# PCB_-_Pro_Micro.net
KiCad netlist of a schematic drawn in EAGLE
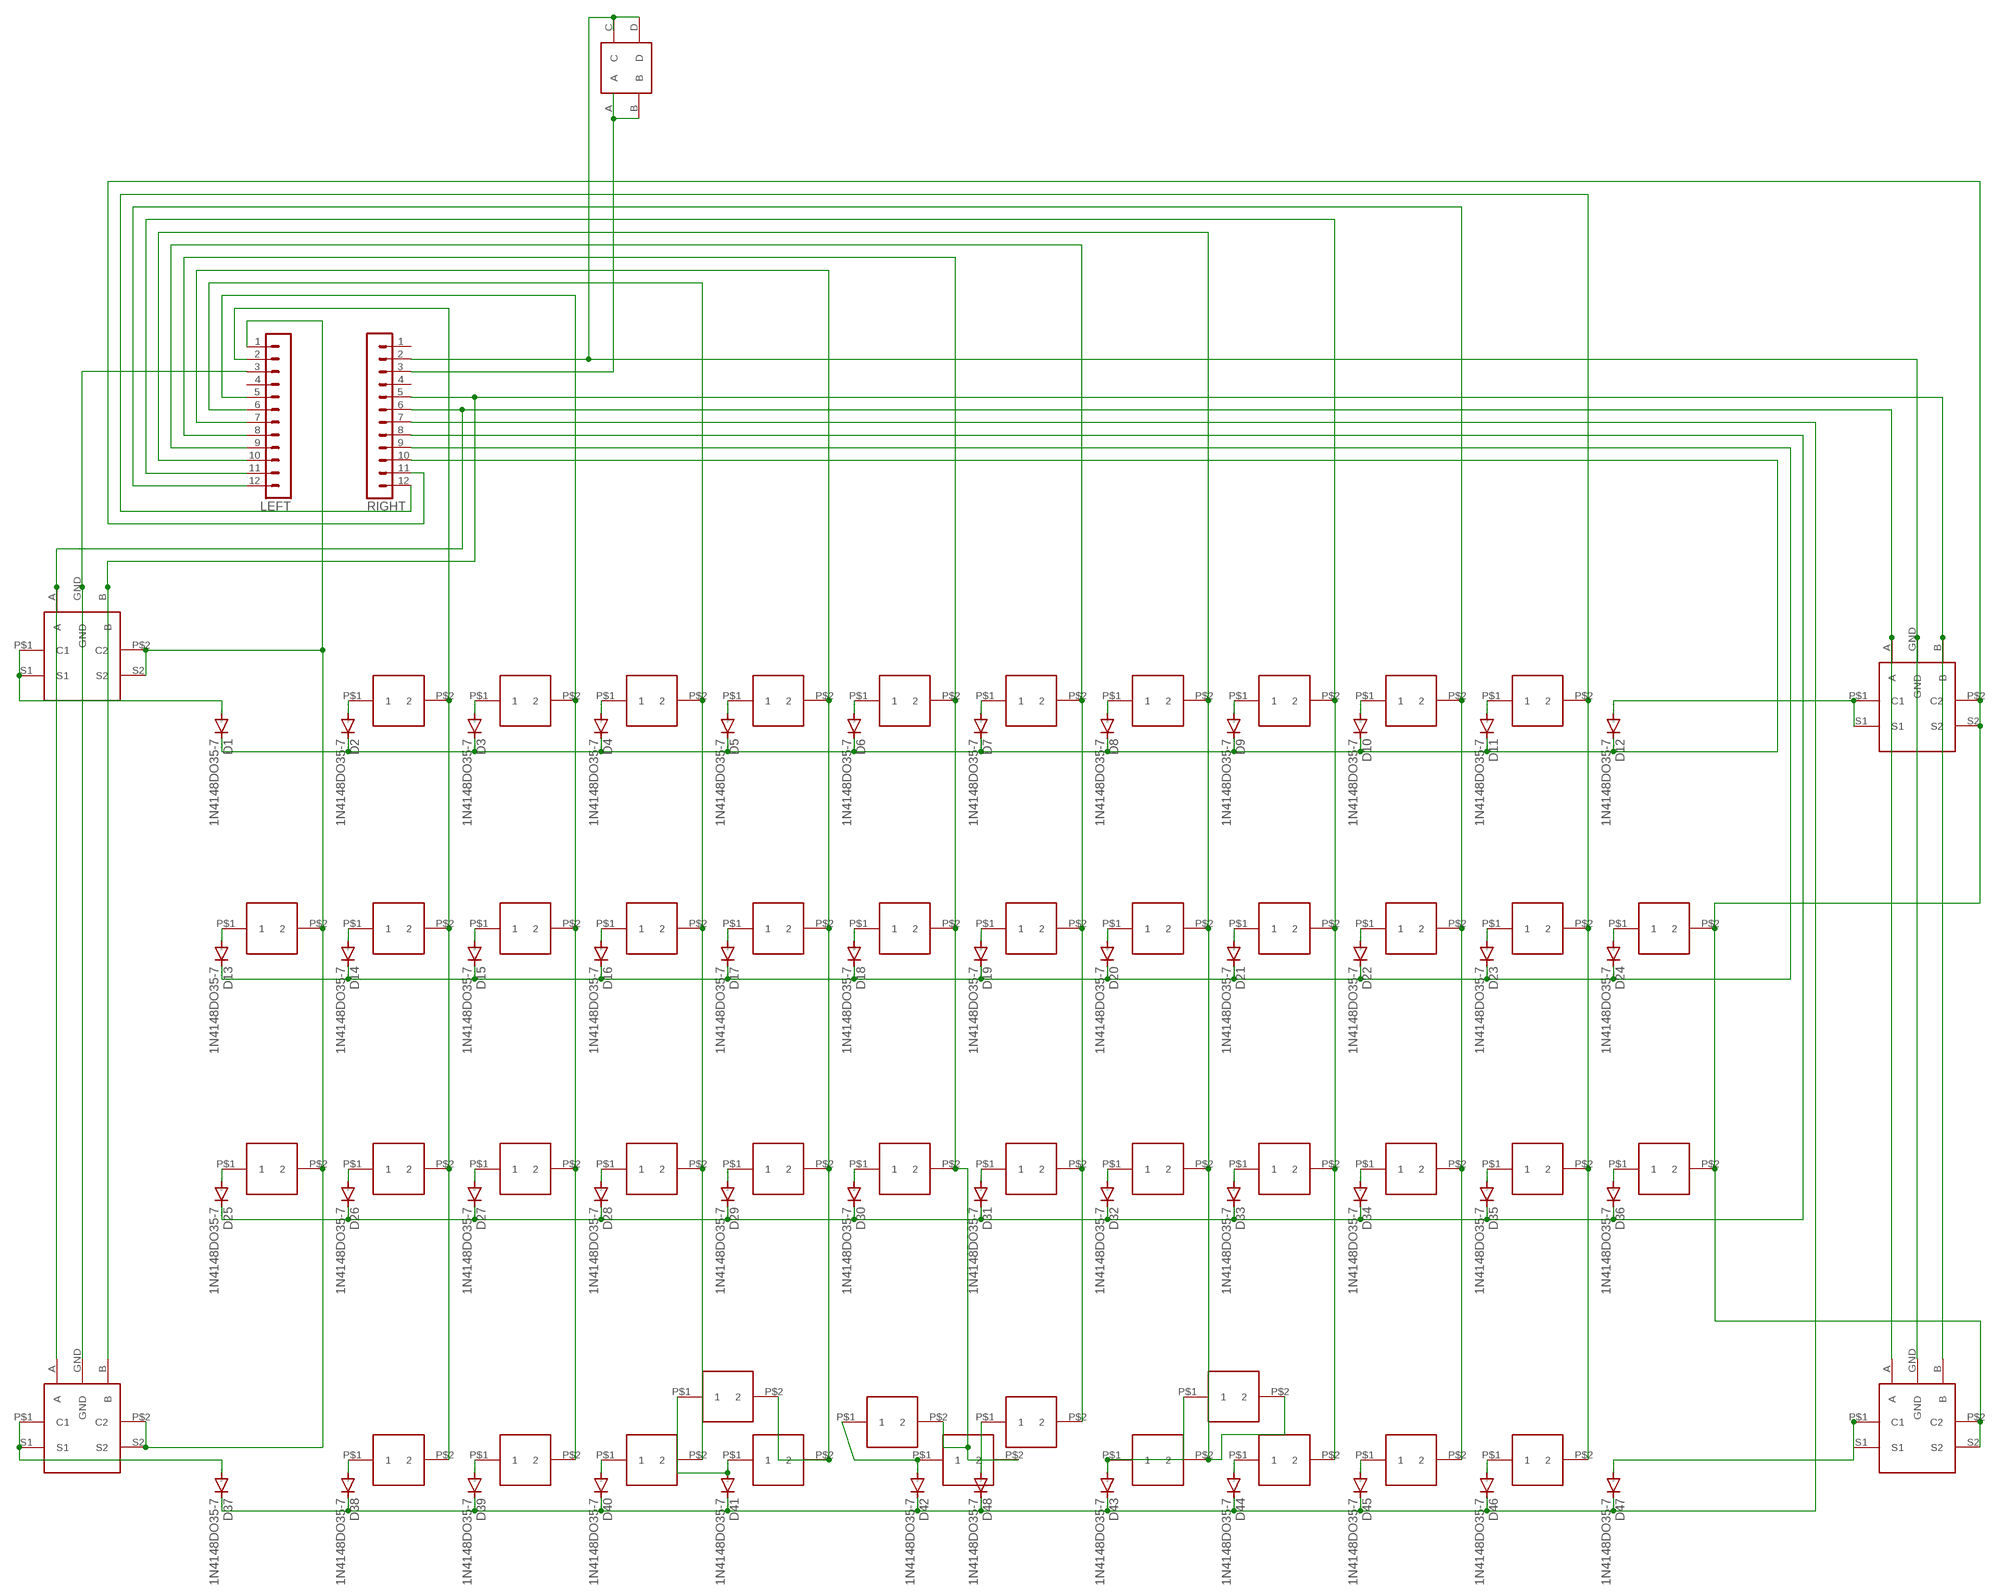
[diagram p0: schematic, sheet 1]

(export (version "E")
  (design (tool "Eeschema 10.0.6"))
  (components
    (comp (ref "1")
      (value "CHERRY-SOLDER")
      (footprint "eagle-import:CHERRY-SOLDER")
      (libsource (lib "eagle-import") (part "CHERRY-SOLDER"))
    )
    (comp (ref "2")
      (value "CHERRY-SOLDER")
      (footprint "eagle-import:CHERRY-SOLDER")
      (libsource (lib "eagle-import") (part "CHERRY-SOLDER"))
    )
    (comp (ref "3")
      (value "CHERRY-SOLDER")
      (footprint "eagle-import:CHERRY-SOLDER")
      (libsource (lib "eagle-import") (part "CHERRY-SOLDER"))
    )
    (comp (ref "4")
      (value "CHERRY-SOLDER")
      (footprint "eagle-import:CHERRY-SOLDER")
      (libsource (lib "eagle-import") (part "CHERRY-SOLDER"))
    )
    (comp (ref "12")
      (value "CHERRY-SOLDER")
      (footprint "eagle-import:CHERRY-SOLDER")
      (libsource (lib "eagle-import") (part "CHERRY-SOLDER"))
    )
    (comp (ref "13")
      (value "CHERRY-SOLDER")
      (footprint "eagle-import:CHERRY-SOLDER")
      (libsource (lib "eagle-import") (part "CHERRY-SOLDER"))
    )
    (comp (ref "14")
      (value "CHERRY-SOLDER")
      (footprint "eagle-import:CHERRY-SOLDER")
      (libsource (lib "eagle-import") (part "CHERRY-SOLDER"))
    )
    (comp (ref "15")
      (value "CHERRY-SOLDER")
      (footprint "eagle-import:CHERRY-SOLDER")
      (libsource (lib "eagle-import") (part "CHERRY-SOLDER"))
    )
    (comp (ref "16")
      (value "CHERRY-SOLDER")
      (footprint "eagle-import:CHERRY-SOLDER")
      (libsource (lib "eagle-import") (part "CHERRY-SOLDER"))
    )
    (comp (ref "17")
      (value "CHERRY-SOLDER")
      (footprint "eagle-import:CHERRY-SOLDER")
      (libsource (lib "eagle-import") (part "CHERRY-SOLDER"))
    )
    (comp (ref "18")
      (value "CHERRY-SOLDER")
      (footprint "eagle-import:CHERRY-SOLDER")
      (libsource (lib "eagle-import") (part "CHERRY-SOLDER"))
    )
    (comp (ref "19")
      (value "CHERRY-SOLDER")
      (footprint "eagle-import:CHERRY-SOLDER")
      (libsource (lib "eagle-import") (part "CHERRY-SOLDER"))
    )
    (comp (ref "21")
      (value "CHERRY-SOLDER")
      (footprint "eagle-import:CHERRY-SOLDER")
      (libsource (lib "eagle-import") (part "CHERRY-SOLDER"))
    )
    (comp (ref "22")
      (value "CHERRY-SOLDER")
      (footprint "eagle-import:CHERRY-SOLDER")
      (libsource (lib "eagle-import") (part "CHERRY-SOLDER"))
    )
    (comp (ref "23")
      (value "CHERRY-SOLDER")
      (footprint "eagle-import:CHERRY-SOLDER")
      (libsource (lib "eagle-import") (part "CHERRY-SOLDER"))
    )
    (comp (ref "24")
      (value "CHERRY-SOLDER")
      (footprint "eagle-import:CHERRY-SOLDER")
      (libsource (lib "eagle-import") (part "CHERRY-SOLDER"))
    )
    (comp (ref "25")
      (value "CHERRY-SOLDER")
      (footprint "eagle-import:CHERRY-SOLDER")
      (libsource (lib "eagle-import") (part "CHERRY-SOLDER"))
    )
    (comp (ref "26")
      (value "CHERRY-SOLDER")
      (footprint "eagle-import:CHERRY-SOLDER")
      (libsource (lib "eagle-import") (part "CHERRY-SOLDER"))
    )
    (comp (ref "27")
      (value "CHERRY-SOLDER")
      (footprint "eagle-import:CHERRY-SOLDER")
      (libsource (lib "eagle-import") (part "CHERRY-SOLDER"))
    )
    (comp (ref "28")
      (value "CHERRY-SOLDER")
      (footprint "eagle-import:CHERRY-SOLDER")
      (libsource (lib "eagle-import") (part "CHERRY-SOLDER"))
    )
    (comp (ref "29")
      (value "CHERRY-SOLDER")
      (footprint "eagle-import:CHERRY-SOLDER")
      (libsource (lib "eagle-import") (part "CHERRY-SOLDER"))
    )
    (comp (ref "31")
      (value "CHERRY-SOLDER")
      (footprint "eagle-import:CHERRY-SOLDER")
      (libsource (lib "eagle-import") (part "CHERRY-SOLDER"))
    )
    (comp (ref "32")
      (value "CHERRY-SOLDER")
      (footprint "eagle-import:CHERRY-SOLDER")
      (libsource (lib "eagle-import") (part "CHERRY-SOLDER"))
    )
    (comp (ref "33")
      (value "CHERRY-SOLDER")
      (footprint "eagle-import:CHERRY-SOLDER")
      (libsource (lib "eagle-import") (part "CHERRY-SOLDER"))
    )
    (comp (ref "34")
      (value "CHERRY-SOLDER")
      (footprint "eagle-import:CHERRY-SOLDER")
      (libsource (lib "eagle-import") (part "CHERRY-SOLDER"))
    )
    (comp (ref "35")
      (value "CHERRY-SOLDER")
      (footprint "eagle-import:CHERRY-SOLDER")
      (libsource (lib "eagle-import") (part "CHERRY-SOLDER"))
    )
    (comp (ref "36")
      (value "CHERRY-SOLDER")
      (footprint "eagle-import:CHERRY-SOLDER")
      (libsource (lib "eagle-import") (part "CHERRY-SOLDER"))
    )
    (comp (ref "37")
      (value "CHERRY-SOLDER")
      (footprint "eagle-import:CHERRY-SOLDER")
      (libsource (lib "eagle-import") (part "CHERRY-SOLDER"))
    )
    (comp (ref "38")
      (value "CHERRY-SOLDER")
      (footprint "eagle-import:CHERRY-SOLDER")
      (libsource (lib "eagle-import") (part "CHERRY-SOLDER"))
    )
    (comp (ref "39")
      (value "CHERRY-SOLDER")
      (footprint "eagle-import:CHERRY-SOLDER")
      (libsource (lib "eagle-import") (part "CHERRY-SOLDER"))
    )
    (comp (ref "42")
      (value "CHERRY-SOLDER")
      (footprint "eagle-import:CHERRY-SOLDER")
      (libsource (lib "eagle-import") (part "CHERRY-SOLDER"))
    )
    (comp (ref "43")
      (value "CHERRY-SOLDER")
      (footprint "eagle-import:CHERRY-SOLDER")
      (libsource (lib "eagle-import") (part "CHERRY-SOLDER"))
    )
    (comp (ref "44")
      (value "CHERRY-SOLDER")
      (footprint "eagle-import:CHERRY-SOLDER")
      (libsource (lib "eagle-import") (part "CHERRY-SOLDER"))
    )
    (comp (ref "45")
      (value "CHERRY-SOLDER")
      (footprint "eagle-import:CHERRY-SOLDER")
      (libsource (lib "eagle-import") (part "CHERRY-SOLDER"))
    )
    (comp (ref "46")
      (value "CHERRY-SOLDER")
      (footprint "eagle-import:CHERRY-SOLDER")
      (libsource (lib "eagle-import") (part "CHERRY-SOLDER"))
    )
    (comp (ref "47")
      (value "CHERRY-SOLDER")
      (footprint "eagle-import:CHERRY-SOLDER")
      (libsource (lib "eagle-import") (part "CHERRY-SOLDER"))
    )
    (comp (ref "48")
      (value "CHERRY-SOLDER")
      (footprint "eagle-import:CHERRY-SOLDER")
      (libsource (lib "eagle-import") (part "CHERRY-SOLDER"))
    )
    (comp (ref "49")
      (value "CHERRY-SOLDER")
      (footprint "eagle-import:CHERRY-SOLDER")
      (libsource (lib "eagle-import") (part "CHERRY-SOLDER"))
    )
    (comp (ref "110")
      (value "CHERRY-SOLDER")
      (footprint "eagle-import:CHERRY-SOLDER")
      (libsource (lib "eagle-import") (part "CHERRY-SOLDER"))
    )
    (comp (ref "111")
      (value "CHERRY-SOLDER")
      (footprint "eagle-import:CHERRY-SOLDER")
      (libsource (lib "eagle-import") (part "CHERRY-SOLDER"))
    )
    (comp (ref "210")
      (value "CHERRY-SOLDER")
      (footprint "eagle-import:CHERRY-SOLDER")
      (libsource (lib "eagle-import") (part "CHERRY-SOLDER"))
    )
    (comp (ref "211")
      (value "CHERRY-SOLDER")
      (footprint "eagle-import:CHERRY-SOLDER")
      (libsource (lib "eagle-import") (part "CHERRY-SOLDER"))
    )
    (comp (ref "212")
      (value "CHERRY-SOLDER")
      (footprint "eagle-import:CHERRY-SOLDER")
      (libsource (lib "eagle-import") (part "CHERRY-SOLDER"))
    )
    (comp (ref "310")
      (value "CHERRY-SOLDER")
      (footprint "eagle-import:CHERRY-SOLDER")
      (libsource (lib "eagle-import") (part "CHERRY-SOLDER"))
    )
    (comp (ref "311")
      (value "CHERRY-SOLDER")
      (footprint "eagle-import:CHERRY-SOLDER")
      (libsource (lib "eagle-import") (part "CHERRY-SOLDER"))
    )
    (comp (ref "312")
      (value "CHERRY-SOLDER")
      (footprint "eagle-import:CHERRY-SOLDER")
      (libsource (lib "eagle-import") (part "CHERRY-SOLDER"))
    )
    (comp (ref "410")
      (value "CHERRY-SOLDER")
      (footprint "eagle-import:CHERRY-SOLDER")
      (libsource (lib "eagle-import") (part "CHERRY-SOLDER"))
    )
    (comp (ref "D1")
      (value "1N4148DO35-7")
      (footprint "eagle-import:DO35-7")
      (libsource (lib "eagle-import") (part "1N4148DO35-7"))
    )
    (comp (ref "D2")
      (value "1N4148DO35-7")
      (footprint "eagle-import:DO35-7")
      (libsource (lib "eagle-import") (part "1N4148DO35-7"))
    )
    (comp (ref "D3")
      (value "1N4148DO35-7")
      (footprint "eagle-import:DO35-7")
      (libsource (lib "eagle-import") (part "1N4148DO35-7"))
    )
    (comp (ref "D4")
      (value "1N4148DO35-7")
      (footprint "eagle-import:DO35-7")
      (libsource (lib "eagle-import") (part "1N4148DO35-7"))
    )
    (comp (ref "D5")
      (value "1N4148DO35-7")
      (footprint "eagle-import:DO35-7")
      (libsource (lib "eagle-import") (part "1N4148DO35-7"))
    )
    (comp (ref "D6")
      (value "1N4148DO35-7")
      (footprint "eagle-import:DO35-7")
      (libsource (lib "eagle-import") (part "1N4148DO35-7"))
    )
    (comp (ref "D7")
      (value "1N4148DO35-7")
      (footprint "eagle-import:DO35-7")
      (libsource (lib "eagle-import") (part "1N4148DO35-7"))
    )
    (comp (ref "D8")
      (value "1N4148DO35-7")
      (footprint "eagle-import:DO35-7")
      (libsource (lib "eagle-import") (part "1N4148DO35-7"))
    )
    (comp (ref "D9")
      (value "1N4148DO35-7")
      (footprint "eagle-import:DO35-7")
      (libsource (lib "eagle-import") (part "1N4148DO35-7"))
    )
    (comp (ref "D10")
      (value "1N4148DO35-7")
      (footprint "eagle-import:DO35-7")
      (libsource (lib "eagle-import") (part "1N4148DO35-7"))
    )
    (comp (ref "D11")
      (value "1N4148DO35-7")
      (footprint "eagle-import:DO35-7")
      (libsource (lib "eagle-import") (part "1N4148DO35-7"))
    )
    (comp (ref "D12")
      (value "1N4148DO35-7")
      (footprint "eagle-import:DO35-7")
      (libsource (lib "eagle-import") (part "1N4148DO35-7"))
    )
    (comp (ref "D13")
      (value "1N4148DO35-7")
      (footprint "eagle-import:DO35-7")
      (libsource (lib "eagle-import") (part "1N4148DO35-7"))
    )
    (comp (ref "D14")
      (value "1N4148DO35-7")
      (footprint "eagle-import:DO35-7")
      (libsource (lib "eagle-import") (part "1N4148DO35-7"))
    )
    (comp (ref "D15")
      (value "1N4148DO35-7")
      (footprint "eagle-import:DO35-7")
      (libsource (lib "eagle-import") (part "1N4148DO35-7"))
    )
    (comp (ref "D16")
      (value "1N4148DO35-7")
      (footprint "eagle-import:DO35-7")
      (libsource (lib "eagle-import") (part "1N4148DO35-7"))
    )
    (comp (ref "D17")
      (value "1N4148DO35-7")
      (footprint "eagle-import:DO35-7")
      (libsource (lib "eagle-import") (part "1N4148DO35-7"))
    )
    (comp (ref "D18")
      (value "1N4148DO35-7")
      (footprint "eagle-import:DO35-7")
      (libsource (lib "eagle-import") (part "1N4148DO35-7"))
    )
    (comp (ref "D19")
      (value "1N4148DO35-7")
      (footprint "eagle-import:DO35-7")
      (libsource (lib "eagle-import") (part "1N4148DO35-7"))
    )
    (comp (ref "D20")
      (value "1N4148DO35-7")
      (footprint "eagle-import:DO35-7")
      (libsource (lib "eagle-import") (part "1N4148DO35-7"))
    )
    (comp (ref "D21")
      (value "1N4148DO35-7")
      (footprint "eagle-import:DO35-7")
      (libsource (lib "eagle-import") (part "1N4148DO35-7"))
    )
    (comp (ref "D22")
      (value "1N4148DO35-7")
      (footprint "eagle-import:DO35-7")
      (libsource (lib "eagle-import") (part "1N4148DO35-7"))
    )
    (comp (ref "D23")
      (value "1N4148DO35-7")
      (footprint "eagle-import:DO35-7")
      (libsource (lib "eagle-import") (part "1N4148DO35-7"))
    )
    (comp (ref "D24")
      (value "1N4148DO35-7")
      (footprint "eagle-import:DO35-7")
      (libsource (lib "eagle-import") (part "1N4148DO35-7"))
    )
    (comp (ref "D25")
      (value "1N4148DO35-7")
      (footprint "eagle-import:DO35-7")
      (libsource (lib "eagle-import") (part "1N4148DO35-7"))
    )
    (comp (ref "D26")
      (value "1N4148DO35-7")
      (footprint "eagle-import:DO35-7")
      (libsource (lib "eagle-import") (part "1N4148DO35-7"))
    )
    (comp (ref "D27")
      (value "1N4148DO35-7")
      (footprint "eagle-import:DO35-7")
      (libsource (lib "eagle-import") (part "1N4148DO35-7"))
    )
    (comp (ref "D28")
      (value "1N4148DO35-7")
      (footprint "eagle-import:DO35-7")
      (libsource (lib "eagle-import") (part "1N4148DO35-7"))
    )
    (comp (ref "D29")
      (value "1N4148DO35-7")
      (footprint "eagle-import:DO35-7")
      (libsource (lib "eagle-import") (part "1N4148DO35-7"))
    )
    (comp (ref "D30")
      (value "1N4148DO35-7")
      (footprint "eagle-import:DO35-7")
      (libsource (lib "eagle-import") (part "1N4148DO35-7"))
    )
    (comp (ref "D31")
      (value "1N4148DO35-7")
      (footprint "eagle-import:DO35-7")
      (libsource (lib "eagle-import") (part "1N4148DO35-7"))
    )
    (comp (ref "D32")
      (value "1N4148DO35-7")
      (footprint "eagle-import:DO35-7")
      (libsource (lib "eagle-import") (part "1N4148DO35-7"))
    )
    (comp (ref "D33")
      (value "1N4148DO35-7")
      (footprint "eagle-import:DO35-7")
      (libsource (lib "eagle-import") (part "1N4148DO35-7"))
    )
    (comp (ref "D34")
      (value "1N4148DO35-7")
      (footprint "eagle-import:DO35-7")
      (libsource (lib "eagle-import") (part "1N4148DO35-7"))
    )
    (comp (ref "D35")
      (value "1N4148DO35-7")
      (footprint "eagle-import:DO35-7")
      (libsource (lib "eagle-import") (part "1N4148DO35-7"))
    )
    (comp (ref "D36")
      (value "1N4148DO35-7")
      (footprint "eagle-import:DO35-7")
      (libsource (lib "eagle-import") (part "1N4148DO35-7"))
    )
    (comp (ref "D37")
      (value "1N4148DO35-7")
      (footprint "eagle-import:DO35-7")
      (libsource (lib "eagle-import") (part "1N4148DO35-7"))
    )
    (comp (ref "D38")
      (value "1N4148DO35-7")
      (footprint "eagle-import:DO35-7")
      (libsource (lib "eagle-import") (part "1N4148DO35-7"))
    )
    (comp (ref "D39")
      (value "1N4148DO35-7")
      (footprint "eagle-import:DO35-7")
      (libsource (lib "eagle-import") (part "1N4148DO35-7"))
    )
    (comp (ref "D40")
      (value "1N4148DO35-7")
      (footprint "eagle-import:DO35-7")
      (libsource (lib "eagle-import") (part "1N4148DO35-7"))
    )
    (comp (ref "D41")
      (value "1N4148DO35-7")
      (footprint "eagle-import:DO35-7")
      (libsource (lib "eagle-import") (part "1N4148DO35-7"))
    )
    (comp (ref "D42")
      (value "1N4148DO35-7")
      (footprint "eagle-import:DO35-7")
      (libsource (lib "eagle-import") (part "1N4148DO35-7"))
    )
    (comp (ref "D43")
      (value "1N4148DO35-7")
      (footprint "eagle-import:DO35-7")
      (libsource (lib "eagle-import") (part "1N4148DO35-7"))
    )
    (comp (ref "D44")
      (value "1N4148DO35-7")
      (footprint "eagle-import:DO35-7")
      (libsource (lib "eagle-import") (part "1N4148DO35-7"))
    )
    (comp (ref "D45")
      (value "1N4148DO35-7")
      (footprint "eagle-import:DO35-7")
      (libsource (lib "eagle-import") (part "1N4148DO35-7"))
    )
    (comp (ref "D46")
      (value "1N4148DO35-7")
      (footprint "eagle-import:DO35-7")
      (libsource (lib "eagle-import") (part "1N4148DO35-7"))
    )
    (comp (ref "D47")
      (value "1N4148DO35-7")
      (footprint "eagle-import:DO35-7")
      (libsource (lib "eagle-import") (part "1N4148DO35-7"))
    )
    (comp (ref "D48")
      (value "1N4148DO35-7")
      (footprint "eagle-import:DO35-7")
      (libsource (lib "eagle-import") (part "1N4148DO35-7"))
    )
    (comp (ref "LEFT")
      (value "MA12-1")
      (footprint "eagle-import:MA12-1")
      (libsource (lib "eagle-import") (part "MA12-1"))
    )
    (comp (ref "RIGHT")
      (value "MA12-1")
      (footprint "eagle-import:MA12-1")
      (libsource (lib "eagle-import") (part "MA12-1"))
    )
    (comp (ref "U$1")
      (value "BUTTON")
      (footprint "eagle-import:BUTTON")
      (libsource (lib "eagle-import") (part "BUTTON"))
    )
    (comp (ref "U$2")
      (value "CHERRY-ENCODER")
      (footprint "eagle-import:CHERRY-ENCODER")
      (libsource (lib "eagle-import") (part "CHERRY-ENCODER"))
    )
    (comp (ref "U$3")
      (value "CHERRY-ENCODER")
      (footprint "eagle-import:CHERRY-ENCODER")
      (libsource (lib "eagle-import") (part "CHERRY-ENCODER"))
    )
    (comp (ref "U$4")
      (value "CHERRY-ENCODER")
      (footprint "eagle-import:CHERRY-ENCODER")
      (libsource (lib "eagle-import") (part "CHERRY-ENCODER"))
    )
    (comp (ref "U$5")
      (value "CHERRY-ENCODER")
      (footprint "eagle-import:CHERRY-ENCODER")
      (libsource (lib "eagle-import") (part "CHERRY-ENCODER"))
    )
  )
  (nets
    (net (code "1") (name "Net-(1-1)") (class "Default")
      (node (ref "1") (pin "P$1") (pinfunction "1_P$1") (pintype "bidirectional"))
      (node (ref "46") (pin "P$1") (pinfunction "1_P$1") (pintype "bidirectional"))
      (node (ref "D42") (pin "A") (pinfunction "A_A") (pintype "passive"))
    )
    (net (code "2") (name "Net-(1-2)") (class "Default")
      (node (ref "1") (pin "P$2") (pinfunction "2_P$2") (pintype "bidirectional"))
      (node (ref "16") (pin "P$2") (pinfunction "2_P$2") (pintype "bidirectional"))
      (node (ref "26") (pin "P$2") (pinfunction "2_P$2") (pintype "bidirectional"))
      (node (ref "36") (pin "P$2") (pinfunction "2_P$2") (pintype "bidirectional"))
      (node (ref "46") (pin "P$2") (pinfunction "2_P$2") (pintype "bidirectional"))
      (node (ref "LEFT") (pin "8") (pinfunction "8_8") (pintype "passive"))
    )
    (net (code "3") (name "Net-(2-1)") (class "Default")
      (node (ref "2") (pin "P$1") (pinfunction "1_P$1") (pintype "bidirectional"))
      (node (ref "D48") (pin "A") (pinfunction "A_A") (pintype "passive"))
    )
    (net (code "4") (name "Net-(3-1)") (class "Default")
      (node (ref "3") (pin "P$1") (pinfunction "1_P$1") (pintype "bidirectional"))
      (node (ref "45") (pin "P$1") (pinfunction "1_P$1") (pintype "bidirectional"))
      (node (ref "D41") (pin "A") (pinfunction "A_A") (pintype "passive"))
    )
    (net (code "5") (name "Net-(4-1)") (class "Default")
      (node (ref "4") (pin "P$1") (pinfunction "1_P$1") (pintype "bidirectional"))
      (node (ref "47") (pin "P$1") (pinfunction "1_P$1") (pintype "bidirectional"))
      (node (ref "D43") (pin "A") (pinfunction "A_A") (pintype "passive"))
    )
    (net (code "6") (name "Net-(12-1)") (class "Default")
      (node (ref "12") (pin "P$1") (pinfunction "1_P$1") (pintype "bidirectional"))
      (node (ref "D2") (pin "A") (pinfunction "A_A") (pintype "passive"))
    )
    (net (code "7") (name "Net-(12-2)") (class "Default")
      (node (ref "12") (pin "P$2") (pinfunction "2_P$2") (pintype "bidirectional"))
      (node (ref "22") (pin "P$2") (pinfunction "2_P$2") (pintype "bidirectional"))
      (node (ref "32") (pin "P$2") (pinfunction "2_P$2") (pintype "bidirectional"))
      (node (ref "42") (pin "P$2") (pinfunction "2_P$2") (pintype "bidirectional"))
      (node (ref "LEFT") (pin "2") (pinfunction "2_2") (pintype "passive"))
    )
    (net (code "8") (name "Net-(13-1)") (class "Default")
      (node (ref "13") (pin "P$1") (pinfunction "1_P$1") (pintype "bidirectional"))
      (node (ref "D3") (pin "A") (pinfunction "A_A") (pintype "passive"))
    )
    (net (code "9") (name "Net-(13-2)") (class "Default")
      (node (ref "13") (pin "P$2") (pinfunction "2_P$2") (pintype "bidirectional"))
      (node (ref "23") (pin "P$2") (pinfunction "2_P$2") (pintype "bidirectional"))
      (node (ref "33") (pin "P$2") (pinfunction "2_P$2") (pintype "bidirectional"))
      (node (ref "43") (pin "P$2") (pinfunction "2_P$2") (pintype "bidirectional"))
      (node (ref "LEFT") (pin "5") (pinfunction "5_5") (pintype "passive"))
    )
    (net (code "10") (name "Net-(14-1)") (class "Default")
      (node (ref "14") (pin "P$1") (pinfunction "1_P$1") (pintype "bidirectional"))
      (node (ref "D4") (pin "A") (pinfunction "A_A") (pintype "passive"))
    )
    (net (code "11") (name "Net-(14-2)") (class "Default")
      (node (ref "14") (pin "P$2") (pinfunction "2_P$2") (pintype "bidirectional"))
      (node (ref "24") (pin "P$2") (pinfunction "2_P$2") (pintype "bidirectional"))
      (node (ref "34") (pin "P$2") (pinfunction "2_P$2") (pintype "bidirectional"))
      (node (ref "44") (pin "P$2") (pinfunction "2_P$2") (pintype "bidirectional"))
      (node (ref "LEFT") (pin "6") (pinfunction "6_6") (pintype "passive"))
    )
    (net (code "12") (name "Net-(15-1)") (class "Default")
      (node (ref "15") (pin "P$1") (pinfunction "1_P$1") (pintype "bidirectional"))
      (node (ref "D5") (pin "A") (pinfunction "A_A") (pintype "passive"))
    )
    (net (code "13") (name "Net-(15-2)") (class "Default")
      (node (ref "15") (pin "P$2") (pinfunction "2_P$2") (pintype "bidirectional"))
      (node (ref "25") (pin "P$2") (pinfunction "2_P$2") (pintype "bidirectional"))
      (node (ref "3") (pin "P$2") (pinfunction "2_P$2") (pintype "bidirectional"))
      (node (ref "35") (pin "P$2") (pinfunction "2_P$2") (pintype "bidirectional"))
      (node (ref "45") (pin "P$2") (pinfunction "2_P$2") (pintype "bidirectional"))
      (node (ref "LEFT") (pin "7") (pinfunction "7_7") (pintype "passive"))
    )
    (net (code "14") (name "Net-(16-1)") (class "Default")
      (node (ref "16") (pin "P$1") (pinfunction "1_P$1") (pintype "bidirectional"))
      (node (ref "D6") (pin "A") (pinfunction "A_A") (pintype "passive"))
    )
    (net (code "15") (name "Net-(17-1)") (class "Default")
      (node (ref "17") (pin "P$1") (pinfunction "1_P$1") (pintype "bidirectional"))
      (node (ref "D7") (pin "A") (pinfunction "A_A") (pintype "passive"))
    )
    (net (code "16") (name "Net-(17-2)") (class "Default")
      (node (ref "17") (pin "P$2") (pinfunction "2_P$2") (pintype "bidirectional"))
      (node (ref "2") (pin "P$2") (pinfunction "2_P$2") (pintype "bidirectional"))
      (node (ref "27") (pin "P$2") (pinfunction "2_P$2") (pintype "bidirectional"))
      (node (ref "37") (pin "P$2") (pinfunction "2_P$2") (pintype "bidirectional"))
      (node (ref "LEFT") (pin "9") (pinfunction "9_9") (pintype "passive"))
    )
    (net (code "17") (name "Net-(18-1)") (class "Default")
      (node (ref "18") (pin "P$1") (pinfunction "1_P$1") (pintype "bidirectional"))
      (node (ref "D8") (pin "A") (pinfunction "A_A") (pintype "passive"))
    )
    (net (code "18") (name "Net-(18-2)") (class "Default")
      (node (ref "18") (pin "P$2") (pinfunction "2_P$2") (pintype "bidirectional"))
      (node (ref "28") (pin "P$2") (pinfunction "2_P$2") (pintype "bidirectional"))
      (node (ref "38") (pin "P$2") (pinfunction "2_P$2") (pintype "bidirectional"))
      (node (ref "4") (pin "P$2") (pinfunction "2_P$2") (pintype "bidirectional"))
      (node (ref "47") (pin "P$2") (pinfunction "2_P$2") (pintype "bidirectional"))
      (node (ref "LEFT") (pin "10") (pinfunction "10_10") (pintype "passive"))
    )
    (net (code "19") (name "Net-(19-1)") (class "Default")
      (node (ref "19") (pin "P$1") (pinfunction "1_P$1") (pintype "bidirectional"))
      (node (ref "D9") (pin "A") (pinfunction "A_A") (pintype "passive"))
    )
    (net (code "20") (name "Net-(19-2)") (class "Default")
      (node (ref "19") (pin "P$2") (pinfunction "2_P$2") (pintype "bidirectional"))
      (node (ref "29") (pin "P$2") (pinfunction "2_P$2") (pintype "bidirectional"))
      (node (ref "39") (pin "P$2") (pinfunction "2_P$2") (pintype "bidirectional"))
      (node (ref "48") (pin "P$2") (pinfunction "2_P$2") (pintype "bidirectional"))
      (node (ref "LEFT") (pin "11") (pinfunction "11_11") (pintype "passive"))
    )
    (net (code "21") (name "Net-(21-1)") (class "Default")
      (node (ref "21") (pin "P$1") (pinfunction "1_P$1") (pintype "bidirectional"))
      (node (ref "D13") (pin "A") (pinfunction "A_A") (pintype "passive"))
    )
    (net (code "22") (name "Net-(21-2)") (class "Default")
      (node (ref "21") (pin "P$2") (pinfunction "2_P$2") (pintype "bidirectional"))
      (node (ref "31") (pin "P$2") (pinfunction "2_P$2") (pintype "bidirectional"))
      (node (ref "LEFT") (pin "1") (pinfunction "1_1") (pintype "passive"))
      (node (ref "U$3") (pin "P$2") (pinfunction "C2_P$2") (pintype "bidirectional"))
      (node (ref "U$3") (pin "S2") (pinfunction "S2_S2") (pintype "bidirectional"))
      (node (ref "U$4") (pin "P$2") (pinfunction "C2_P$2") (pintype "bidirectional"))
      (node (ref "U$4") (pin "S2") (pinfunction "S2_S2") (pintype "bidirectional"))
    )
    (net (code "23") (name "Net-(22-1)") (class "Default")
      (node (ref "22") (pin "P$1") (pinfunction "1_P$1") (pintype "bidirectional"))
      (node (ref "D14") (pin "A") (pinfunction "A_A") (pintype "passive"))
    )
    (net (code "24") (name "Net-(23-1)") (class "Default")
      (node (ref "23") (pin "P$1") (pinfunction "1_P$1") (pintype "bidirectional"))
      (node (ref "D15") (pin "A") (pinfunction "A_A") (pintype "passive"))
    )
    (net (code "25") (name "Net-(24-1)") (class "Default")
      (node (ref "24") (pin "P$1") (pinfunction "1_P$1") (pintype "bidirectional"))
      (node (ref "D16") (pin "A") (pinfunction "A_A") (pintype "passive"))
    )
    (net (code "26") (name "Net-(25-1)") (class "Default")
      (node (ref "25") (pin "P$1") (pinfunction "1_P$1") (pintype "bidirectional"))
      (node (ref "D17") (pin "A") (pinfunction "A_A") (pintype "passive"))
    )
    (net (code "27") (name "Net-(26-1)") (class "Default")
      (node (ref "26") (pin "P$1") (pinfunction "1_P$1") (pintype "bidirectional"))
      (node (ref "D18") (pin "A") (pinfunction "A_A") (pintype "passive"))
    )
    (net (code "28") (name "Net-(27-1)") (class "Default")
      (node (ref "27") (pin "P$1") (pinfunction "1_P$1") (pintype "bidirectional"))
      (node (ref "D19") (pin "A") (pinfunction "A_A") (pintype "passive"))
    )
    (net (code "29") (name "Net-(28-1)") (class "Default")
      (node (ref "28") (pin "P$1") (pinfunction "1_P$1") (pintype "bidirectional"))
      (node (ref "D20") (pin "A") (pinfunction "A_A") (pintype "passive"))
    )
    (net (code "30") (name "Net-(29-1)") (class "Default")
      (node (ref "29") (pin "P$1") (pinfunction "1_P$1") (pintype "bidirectional"))
      (node (ref "D21") (pin "A") (pinfunction "A_A") (pintype "passive"))
    )
    (net (code "31") (name "Net-(31-1)") (class "Default")
      (node (ref "31") (pin "P$1") (pinfunction "1_P$1") (pintype "bidirectional"))
      (node (ref "D25") (pin "A") (pinfunction "A_A") (pintype "passive"))
    )
    (net (code "32") (name "Net-(32-1)") (class "Default")
      (node (ref "32") (pin "P$1") (pinfunction "1_P$1") (pintype "bidirectional"))
      (node (ref "D26") (pin "A") (pinfunction "A_A") (pintype "passive"))
    )
    (net (code "33") (name "Net-(33-1)") (class "Default")
      (node (ref "33") (pin "P$1") (pinfunction "1_P$1") (pintype "bidirectional"))
      (node (ref "D27") (pin "A") (pinfunction "A_A") (pintype "passive"))
    )
    (net (code "34") (name "Net-(34-1)") (class "Default")
      (node (ref "34") (pin "P$1") (pinfunction "1_P$1") (pintype "bidirectional"))
      (node (ref "D28") (pin "A") (pinfunction "A_A") (pintype "passive"))
    )
    (net (code "35") (name "Net-(35-1)") (class "Default")
      (node (ref "35") (pin "P$1") (pinfunction "1_P$1") (pintype "bidirectional"))
      (node (ref "D29") (pin "A") (pinfunction "A_A") (pintype "passive"))
    )
    (net (code "36") (name "Net-(36-1)") (class "Default")
      (node (ref "36") (pin "P$1") (pinfunction "1_P$1") (pintype "bidirectional"))
      (node (ref "D30") (pin "A") (pinfunction "A_A") (pintype "passive"))
    )
    (net (code "37") (name "Net-(37-1)") (class "Default")
      (node (ref "37") (pin "P$1") (pinfunction "1_P$1") (pintype "bidirectional"))
      (node (ref "D31") (pin "A") (pinfunction "A_A") (pintype "passive"))
    )
    (net (code "38") (name "Net-(38-1)") (class "Default")
      (node (ref "38") (pin "P$1") (pinfunction "1_P$1") (pintype "bidirectional"))
      (node (ref "D32") (pin "A") (pinfunction "A_A") (pintype "passive"))
    )
    (net (code "39") (name "Net-(39-1)") (class "Default")
      (node (ref "39") (pin "P$1") (pinfunction "1_P$1") (pintype "bidirectional"))
      (node (ref "D33") (pin "A") (pinfunction "A_A") (pintype "passive"))
    )
    (net (code "40") (name "Net-(42-1)") (class "Default")
      (node (ref "42") (pin "P$1") (pinfunction "1_P$1") (pintype "bidirectional"))
      (node (ref "D38") (pin "A") (pinfunction "A_A") (pintype "passive"))
    )
    (net (code "41") (name "Net-(43-1)") (class "Default")
      (node (ref "43") (pin "P$1") (pinfunction "1_P$1") (pintype "bidirectional"))
      (node (ref "D39") (pin "A") (pinfunction "A_A") (pintype "passive"))
    )
    (net (code "42") (name "Net-(44-1)") (class "Default")
      (node (ref "44") (pin "P$1") (pinfunction "1_P$1") (pintype "bidirectional"))
      (node (ref "D40") (pin "A") (pinfunction "A_A") (pintype "passive"))
    )
    (net (code "43") (name "Net-(48-1)") (class "Default")
      (node (ref "48") (pin "P$1") (pinfunction "1_P$1") (pintype "bidirectional"))
      (node (ref "D44") (pin "A") (pinfunction "A_A") (pintype "passive"))
    )
    (net (code "44") (name "Net-(49-1)") (class "Default")
      (node (ref "49") (pin "P$1") (pinfunction "1_P$1") (pintype "bidirectional"))
      (node (ref "D45") (pin "A") (pinfunction "A_A") (pintype "passive"))
    )
    (net (code "45") (name "Net-(110-1)") (class "Default")
      (node (ref "110") (pin "P$1") (pinfunction "1_P$1") (pintype "bidirectional"))
      (node (ref "D10") (pin "A") (pinfunction "A_A") (pintype "passive"))
    )
    (net (code "46") (name "Net-(110-2)") (class "Default")
      (node (ref "110") (pin "P$2") (pinfunction "2_P$2") (pintype "bidirectional"))
      (node (ref "210") (pin "P$2") (pinfunction "2_P$2") (pintype "bidirectional"))
      (node (ref "310") (pin "P$2") (pinfunction "2_P$2") (pintype "bidirectional"))
      (node (ref "49") (pin "P$2") (pinfunction "2_P$2") (pintype "bidirectional"))
      (node (ref "LEFT") (pin "12") (pinfunction "12_12") (pintype "passive"))
    )
    (net (code "47") (name "Net-(111-1)") (class "Default")
      (node (ref "111") (pin "P$1") (pinfunction "1_P$1") (pintype "bidirectional"))
      (node (ref "D11") (pin "A") (pinfunction "A_A") (pintype "passive"))
    )
    (net (code "48") (name "Net-(111-2)") (class "Default")
      (node (ref "111") (pin "P$2") (pinfunction "2_P$2") (pintype "bidirectional"))
      (node (ref "211") (pin "P$2") (pinfunction "2_P$2") (pintype "bidirectional"))
      (node (ref "311") (pin "P$2") (pinfunction "2_P$2") (pintype "bidirectional"))
      (node (ref "410") (pin "P$2") (pinfunction "2_P$2") (pintype "bidirectional"))
      (node (ref "RIGHT") (pin "12") (pinfunction "12_12") (pintype "passive"))
    )
    (net (code "49") (name "Net-(210-1)") (class "Default")
      (node (ref "210") (pin "P$1") (pinfunction "1_P$1") (pintype "bidirectional"))
      (node (ref "D22") (pin "A") (pinfunction "A_A") (pintype "passive"))
    )
    (net (code "50") (name "Net-(211-1)") (class "Default")
      (node (ref "211") (pin "P$1") (pinfunction "1_P$1") (pintype "bidirectional"))
      (node (ref "D23") (pin "A") (pinfunction "A_A") (pintype "passive"))
    )
    (net (code "51") (name "Net-(212-1)") (class "Default")
      (node (ref "212") (pin "P$1") (pinfunction "1_P$1") (pintype "bidirectional"))
      (node (ref "D24") (pin "A") (pinfunction "A_A") (pintype "passive"))
    )
    (net (code "52") (name "Net-(212-2)") (class "Default")
      (node (ref "212") (pin "P$2") (pinfunction "2_P$2") (pintype "bidirectional"))
      (node (ref "312") (pin "P$2") (pinfunction "2_P$2") (pintype "bidirectional"))
      (node (ref "RIGHT") (pin "11") (pinfunction "11_11") (pintype "passive"))
      (node (ref "U$2") (pin "P$2") (pinfunction "C2_P$2") (pintype "bidirectional"))
      (node (ref "U$2") (pin "S2") (pinfunction "S2_S2") (pintype "bidirectional"))
      (node (ref "U$5") (pin "P$2") (pinfunction "C2_P$2") (pintype "bidirectional"))
      (node (ref "U$5") (pin "S2") (pinfunction "S2_S2") (pintype "bidirectional"))
    )
    (net (code "53") (name "Net-(310-1)") (class "Default")
      (node (ref "310") (pin "P$1") (pinfunction "1_P$1") (pintype "bidirectional"))
      (node (ref "D34") (pin "A") (pinfunction "A_A") (pintype "passive"))
    )
    (net (code "54") (name "Net-(311-1)") (class "Default")
      (node (ref "311") (pin "P$1") (pinfunction "1_P$1") (pintype "bidirectional"))
      (node (ref "D35") (pin "A") (pinfunction "A_A") (pintype "passive"))
    )
    (net (code "55") (name "Net-(312-1)") (class "Default")
      (node (ref "312") (pin "P$1") (pinfunction "1_P$1") (pintype "bidirectional"))
      (node (ref "D36") (pin "A") (pinfunction "A_A") (pintype "passive"))
    )
    (net (code "56") (name "Net-(410-1)") (class "Default")
      (node (ref "410") (pin "P$1") (pinfunction "1_P$1") (pintype "bidirectional"))
      (node (ref "D46") (pin "A") (pinfunction "A_A") (pintype "passive"))
    )
    (net (code "57") (name "Net-(D1-PadC)") (class "Default")
      (node (ref "D1") (pin "C") (pinfunction "C_C") (pintype "passive"))
      (node (ref "D10") (pin "C") (pinfunction "C_C") (pintype "passive"))
      (node (ref "D11") (pin "C") (pinfunction "C_C") (pintype "passive"))
      (node (ref "D12") (pin "C") (pinfunction "C_C") (pintype "passive"))
      (node (ref "D2") (pin "C") (pinfunction "C_C") (pintype "passive"))
      (node (ref "D3") (pin "C") (pinfunction "C_C") (pintype "passive"))
      (node (ref "D4") (pin "C") (pinfunction "C_C") (pintype "passive"))
      (node (ref "D5") (pin "C") (pinfunction "C_C") (pintype "passive"))
      (node (ref "D6") (pin "C") (pinfunction "C_C") (pintype "passive"))
      (node (ref "D7") (pin "C") (pinfunction "C_C") (pintype "passive"))
      (node (ref "D8") (pin "C") (pinfunction "C_C") (pintype "passive"))
      (node (ref "D9") (pin "C") (pinfunction "C_C") (pintype "passive"))
      (node (ref "RIGHT") (pin "10") (pinfunction "10_10") (pintype "passive"))
    )
    (net (code "58") (name "Net-(D13-PadC)") (class "Default")
      (node (ref "D13") (pin "C") (pinfunction "C_C") (pintype "passive"))
      (node (ref "D14") (pin "C") (pinfunction "C_C") (pintype "passive"))
      (node (ref "D15") (pin "C") (pinfunction "C_C") (pintype "passive"))
      (node (ref "D16") (pin "C") (pinfunction "C_C") (pintype "passive"))
      (node (ref "D17") (pin "C") (pinfunction "C_C") (pintype "passive"))
      (node (ref "D18") (pin "C") (pinfunction "C_C") (pintype "passive"))
      (node (ref "D19") (pin "C") (pinfunction "C_C") (pintype "passive"))
      (node (ref "D20") (pin "C") (pinfunction "C_C") (pintype "passive"))
      (node (ref "D21") (pin "C") (pinfunction "C_C") (pintype "passive"))
      (node (ref "D22") (pin "C") (pinfunction "C_C") (pintype "passive"))
      (node (ref "D23") (pin "C") (pinfunction "C_C") (pintype "passive"))
      (node (ref "D24") (pin "C") (pinfunction "C_C") (pintype "passive"))
      (node (ref "RIGHT") (pin "9") (pinfunction "9_9") (pintype "passive"))
    )
    (net (code "59") (name "Net-(D25-PadC)") (class "Default")
      (node (ref "D25") (pin "C") (pinfunction "C_C") (pintype "passive"))
      (node (ref "D26") (pin "C") (pinfunction "C_C") (pintype "passive"))
      (node (ref "D27") (pin "C") (pinfunction "C_C") (pintype "passive"))
      (node (ref "D28") (pin "C") (pinfunction "C_C") (pintype "passive"))
      (node (ref "D29") (pin "C") (pinfunction "C_C") (pintype "passive"))
      (node (ref "D30") (pin "C") (pinfunction "C_C") (pintype "passive"))
      (node (ref "D31") (pin "C") (pinfunction "C_C") (pintype "passive"))
      (node (ref "D32") (pin "C") (pinfunction "C_C") (pintype "passive"))
      (node (ref "D33") (pin "C") (pinfunction "C_C") (pintype "passive"))
      (node (ref "D34") (pin "C") (pinfunction "C_C") (pintype "passive"))
      (node (ref "D35") (pin "C") (pinfunction "C_C") (pintype "passive"))
      (node (ref "D36") (pin "C") (pinfunction "C_C") (pintype "passive"))
      (node (ref "RIGHT") (pin "8") (pinfunction "8_8") (pintype "passive"))
    )
    (net (code "60") (name "Net-(D37-PadC)") (class "Default")
      (node (ref "D37") (pin "C") (pinfunction "C_C") (pintype "passive"))
      (node (ref "D38") (pin "C") (pinfunction "C_C") (pintype "passive"))
      (node (ref "D39") (pin "C") (pinfunction "C_C") (pintype "passive"))
      (node (ref "D40") (pin "C") (pinfunction "C_C") (pintype "passive"))
      (node (ref "D41") (pin "C") (pinfunction "C_C") (pintype "passive"))
      (node (ref "D42") (pin "C") (pinfunction "C_C") (pintype "passive"))
      (node (ref "D43") (pin "C") (pinfunction "C_C") (pintype "passive"))
      (node (ref "D44") (pin "C") (pinfunction "C_C") (pintype "passive"))
      (node (ref "D45") (pin "C") (pinfunction "C_C") (pintype "passive"))
      (node (ref "D46") (pin "C") (pinfunction "C_C") (pintype "passive"))
      (node (ref "D47") (pin "C") (pinfunction "C_C") (pintype "passive"))
      (node (ref "D48") (pin "C") (pinfunction "C_C") (pintype "passive"))
      (node (ref "RIGHT") (pin "7") (pinfunction "7_7") (pintype "passive"))
    )
    (net (code "61") (name "Net-(LEFT-Pad3)") (class "Default")
      (node (ref "LEFT") (pin "3") (pinfunction "3_3") (pintype "passive"))
      (node (ref "U$3") (pin "GND") (pinfunction "GND_GND") (pintype "bidirectional"))
      (node (ref "U$4") (pin "GND") (pinfunction "GND_GND") (pintype "bidirectional"))
    )
    (net (code "62") (name "Net-(RIGHT-Pad2)") (class "Default")
      (node (ref "RIGHT") (pin "2") (pinfunction "2_2") (pintype "passive"))
      (node (ref "U$1") (pin "C") (pinfunction "C_C") (pintype "bidirectional"))
      (node (ref "U$1") (pin "D") (pinfunction "D_D") (pintype "bidirectional"))
      (node (ref "U$2") (pin "GND") (pinfunction "GND_GND") (pintype "bidirectional"))
      (node (ref "U$5") (pin "GND") (pinfunction "GND_GND") (pintype "bidirectional"))
    )
    (net (code "63") (name "Net-(RIGHT-Pad3)") (class "Default")
      (node (ref "RIGHT") (pin "3") (pinfunction "3_3") (pintype "passive"))
      (node (ref "U$1") (pin "A") (pinfunction "A_A") (pintype "bidirectional"))
      (node (ref "U$1") (pin "B") (pinfunction "B_B") (pintype "bidirectional"))
    )
    (net (code "64") (name "Net-(RIGHT-Pad5)") (class "Default")
      (node (ref "RIGHT") (pin "5") (pinfunction "5_5") (pintype "passive"))
      (node (ref "U$2") (pin "B") (pinfunction "B_B") (pintype "bidirectional"))
      (node (ref "U$3") (pin "B") (pinfunction "B_B") (pintype "bidirectional"))
      (node (ref "U$4") (pin "B") (pinfunction "B_B") (pintype "bidirectional"))
      (node (ref "U$5") (pin "B") (pinfunction "B_B") (pintype "bidirectional"))
    )
    (net (code "65") (name "Net-(RIGHT-Pad6)") (class "Default")
      (node (ref "RIGHT") (pin "6") (pinfunction "6_6") (pintype "passive"))
      (node (ref "U$2") (pin "A") (pinfunction "A_A") (pintype "bidirectional"))
      (node (ref "U$3") (pin "A") (pinfunction "A_A") (pintype "bidirectional"))
      (node (ref "U$4") (pin "A") (pinfunction "A_A") (pintype "bidirectional"))
      (node (ref "U$5") (pin "A") (pinfunction "A_A") (pintype "bidirectional"))
    )
    (net (code "66") (name "Net-(U$2-C1)") (class "Default")
      (node (ref "D12") (pin "A") (pinfunction "A_A") (pintype "passive"))
      (node (ref "U$2") (pin "P$1") (pinfunction "C1_P$1") (pintype "bidirectional"))
      (node (ref "U$2") (pin "S1") (pinfunction "S1_S1") (pintype "bidirectional"))
    )
    (net (code "67") (name "Net-(U$3-C1)") (class "Default")
      (node (ref "D1") (pin "A") (pinfunction "A_A") (pintype "passive"))
      (node (ref "U$3") (pin "P$1") (pinfunction "C1_P$1") (pintype "bidirectional"))
      (node (ref "U$3") (pin "S1") (pinfunction "S1_S1") (pintype "bidirectional"))
    )
    (net (code "68") (name "Net-(U$4-C1)") (class "Default")
      (node (ref "D37") (pin "A") (pinfunction "A_A") (pintype "passive"))
      (node (ref "U$4") (pin "P$1") (pinfunction "C1_P$1") (pintype "bidirectional"))
      (node (ref "U$4") (pin "S1") (pinfunction "S1_S1") (pintype "bidirectional"))
    )
    (net (code "69") (name "Net-(U$5-C1)") (class "Default")
      (node (ref "D47") (pin "A") (pinfunction "A_A") (pintype "passive"))
      (node (ref "U$5") (pin "P$1") (pinfunction "C1_P$1") (pintype "bidirectional"))
      (node (ref "U$5") (pin "S1") (pinfunction "S1_S1") (pintype "bidirectional"))
    )
    (net (code "70") (name "unconnected-(LEFT-Pad4)") (class "Default")
      (node (ref "LEFT") (pin "4") (pinfunction "4_4") (pintype "passive"))
    )
    (net (code "71") (name "unconnected-(RIGHT-Pad1)") (class "Default")
      (node (ref "RIGHT") (pin "1") (pinfunction "1_1") (pintype "passive"))
    )
    (net (code "72") (name "unconnected-(RIGHT-Pad4)") (class "Default")
      (node (ref "RIGHT") (pin "4") (pinfunction "4_4") (pintype "passive"))
    )
  )
)
